# Current_Limit.net
KiCad netlist of a schematic drawn in Altium Designer
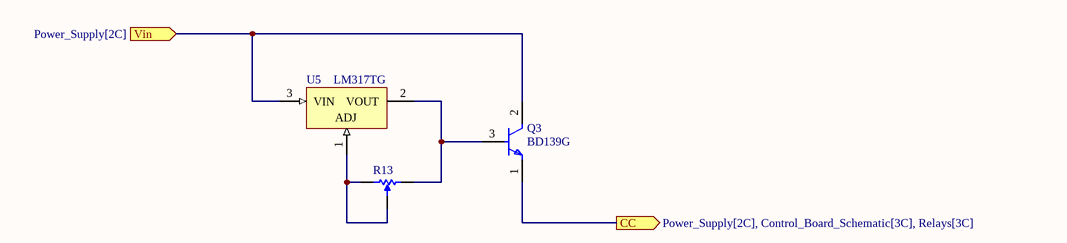
[diagram p0: Current_Limit.SchDoc]

(export (version "E")
  (design (tool "Eeschema 10.0.6"))
  (components
    (comp (ref "Q3")
      (value "BD139G")
      (footprint "FP-77-09-MFG")
      (description "1.5 A, 80 V NPN Power Bipolar Junction Transistor. ONSSPCTRNSTLT1T0R;")
      (libsource (lib "Konstantinos Psarras") (part "2239aae8d27e6eb6063ebea98827daf"))
    )
    (comp (ref "R13")
      (value "3296W-1-102LF")
      (footprint "BOUR-3296W-1-3")
      (description "Square Trimpot(R) Trimming Potentiometer, 1000 Ohm, -55 to 125 degC, 3-Pin THD, RoHS, Tube")
      (fields (field (name "MANUFACTURER") "Bourns") (field (name "POWER") "500mW"))
      (libsource (lib "Konstantinos Psarras") (part "RES-ADJ-3"))
    )
    (comp (ref "U5")
      (value "LM317TG")
      (footprint "ONSC-TO-220-3-221AB-01")
      (fields (field (name "MANUFACTURER") "ON Semiconductor"))
      (libsource (lib "Konstantinos Psarras") (part "ONSC-LM317TG-3"))
    )
  )
  (nets
    (net (code "1") (name "/CC") (class "Default")
      (node (ref "Q3") (pin "1") (pinfunction "E_1") (pintype "passive"))
    )
    (net (code "2") (name "/Vin") (class "Default")
      (node (ref "Q3") (pin "2") (pinfunction "C_2") (pintype "passive"))
      (node (ref "U5") (pin "3") (pinfunction "VIN_3") (pintype "input"))
    )
    (net (code "3") (name "Net-(Q3-B)") (class "Default")
      (node (ref "Q3") (pin "3") (pinfunction "B_3") (pintype "passive"))
      (node (ref "R13") (pin "2") (pinfunction "B_2") (pintype "passive"))
      (node (ref "U5") (pin "2") (pinfunction "VOUT_2") (pintype "power_in"))
    )
    (net (code "4") (name "Net-(R13-A)") (class "Default")
      (node (ref "R13") (pin "1") (pinfunction "A_1") (pintype "passive"))
      (node (ref "R13") (pin "3") (pinfunction "TAP_3") (pintype "passive"))
      (node (ref "U5") (pin "1") (pinfunction "ADJ_1") (pintype "input"))
    )
  )
)
